# OPB625_Optical_SW_Breakout.net
KiCad netlist of a schematic drawn in EAGLE
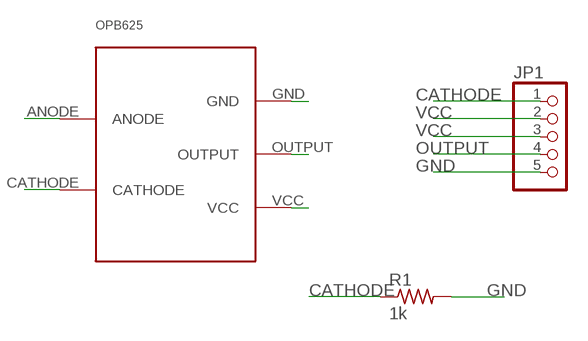
[diagram p0: schematic, sheet 1]

(export (version "E")
  (design (tool "Eeschema 10.0.6"))
  (components
    (comp (ref "JP1")
      (value "PINHD-1X5")
      (footprint "eagle-import:1X05")
      (libsource (lib "eagle-import") (part "PINHD-1X5"))
    )
    (comp (ref "R1")
      (value "1k")
      (footprint "eagle-import:R0805")
      (libsource (lib "eagle-import") (part "R-US_R0805"))
    )
    (comp (ref "U$1")
      (value "OPB625")
      (footprint "eagle-import:OPB625")
      (libsource (lib "eagle-import") (part "OPB625"))
    )
  )
  (nets
    (net (code "1") (name "/CATHODE") (class "Default")
      (node (ref "JP1") (pin "1") (pinfunction "1_1") (pintype "passive"))
      (node (ref "R1") (pin "1") (pinfunction "1_1") (pintype "passive"))
      (node (ref "U$1") (pin "CATHODE") (pinfunction "CATHODE_CATHODE") (pintype "bidirectional"))
    )
    (net (code "2") (name "/GND") (class "Default")
      (node (ref "JP1") (pin "5") (pinfunction "5_5") (pintype "passive"))
      (node (ref "R1") (pin "2") (pinfunction "2_2") (pintype "passive"))
      (node (ref "U$1") (pin "GND") (pinfunction "GND_GND") (pintype "bidirectional"))
    )
    (net (code "3") (name "/OUTPUT") (class "Default")
      (node (ref "JP1") (pin "4") (pinfunction "4_4") (pintype "passive"))
      (node (ref "U$1") (pin "OUTPUT") (pinfunction "OUTPUT_OUTPUT") (pintype "bidirectional"))
    )
    (net (code "4") (name "/VCC") (class "Default")
      (node (ref "JP1") (pin "2") (pinfunction "2_2") (pintype "passive"))
      (node (ref "JP1") (pin "3") (pinfunction "3_3") (pintype "passive"))
      (node (ref "U$1") (pin "ANODE") (pinfunction "ANODE_ANODE") (pintype "bidirectional"))
      (node (ref "U$1") (pin "VCC") (pinfunction "VCC_VCC") (pintype "bidirectional"))
    )
  )
)
